# sunsensor.net
KiCad netlist of a schematic drawn in Altium Designer
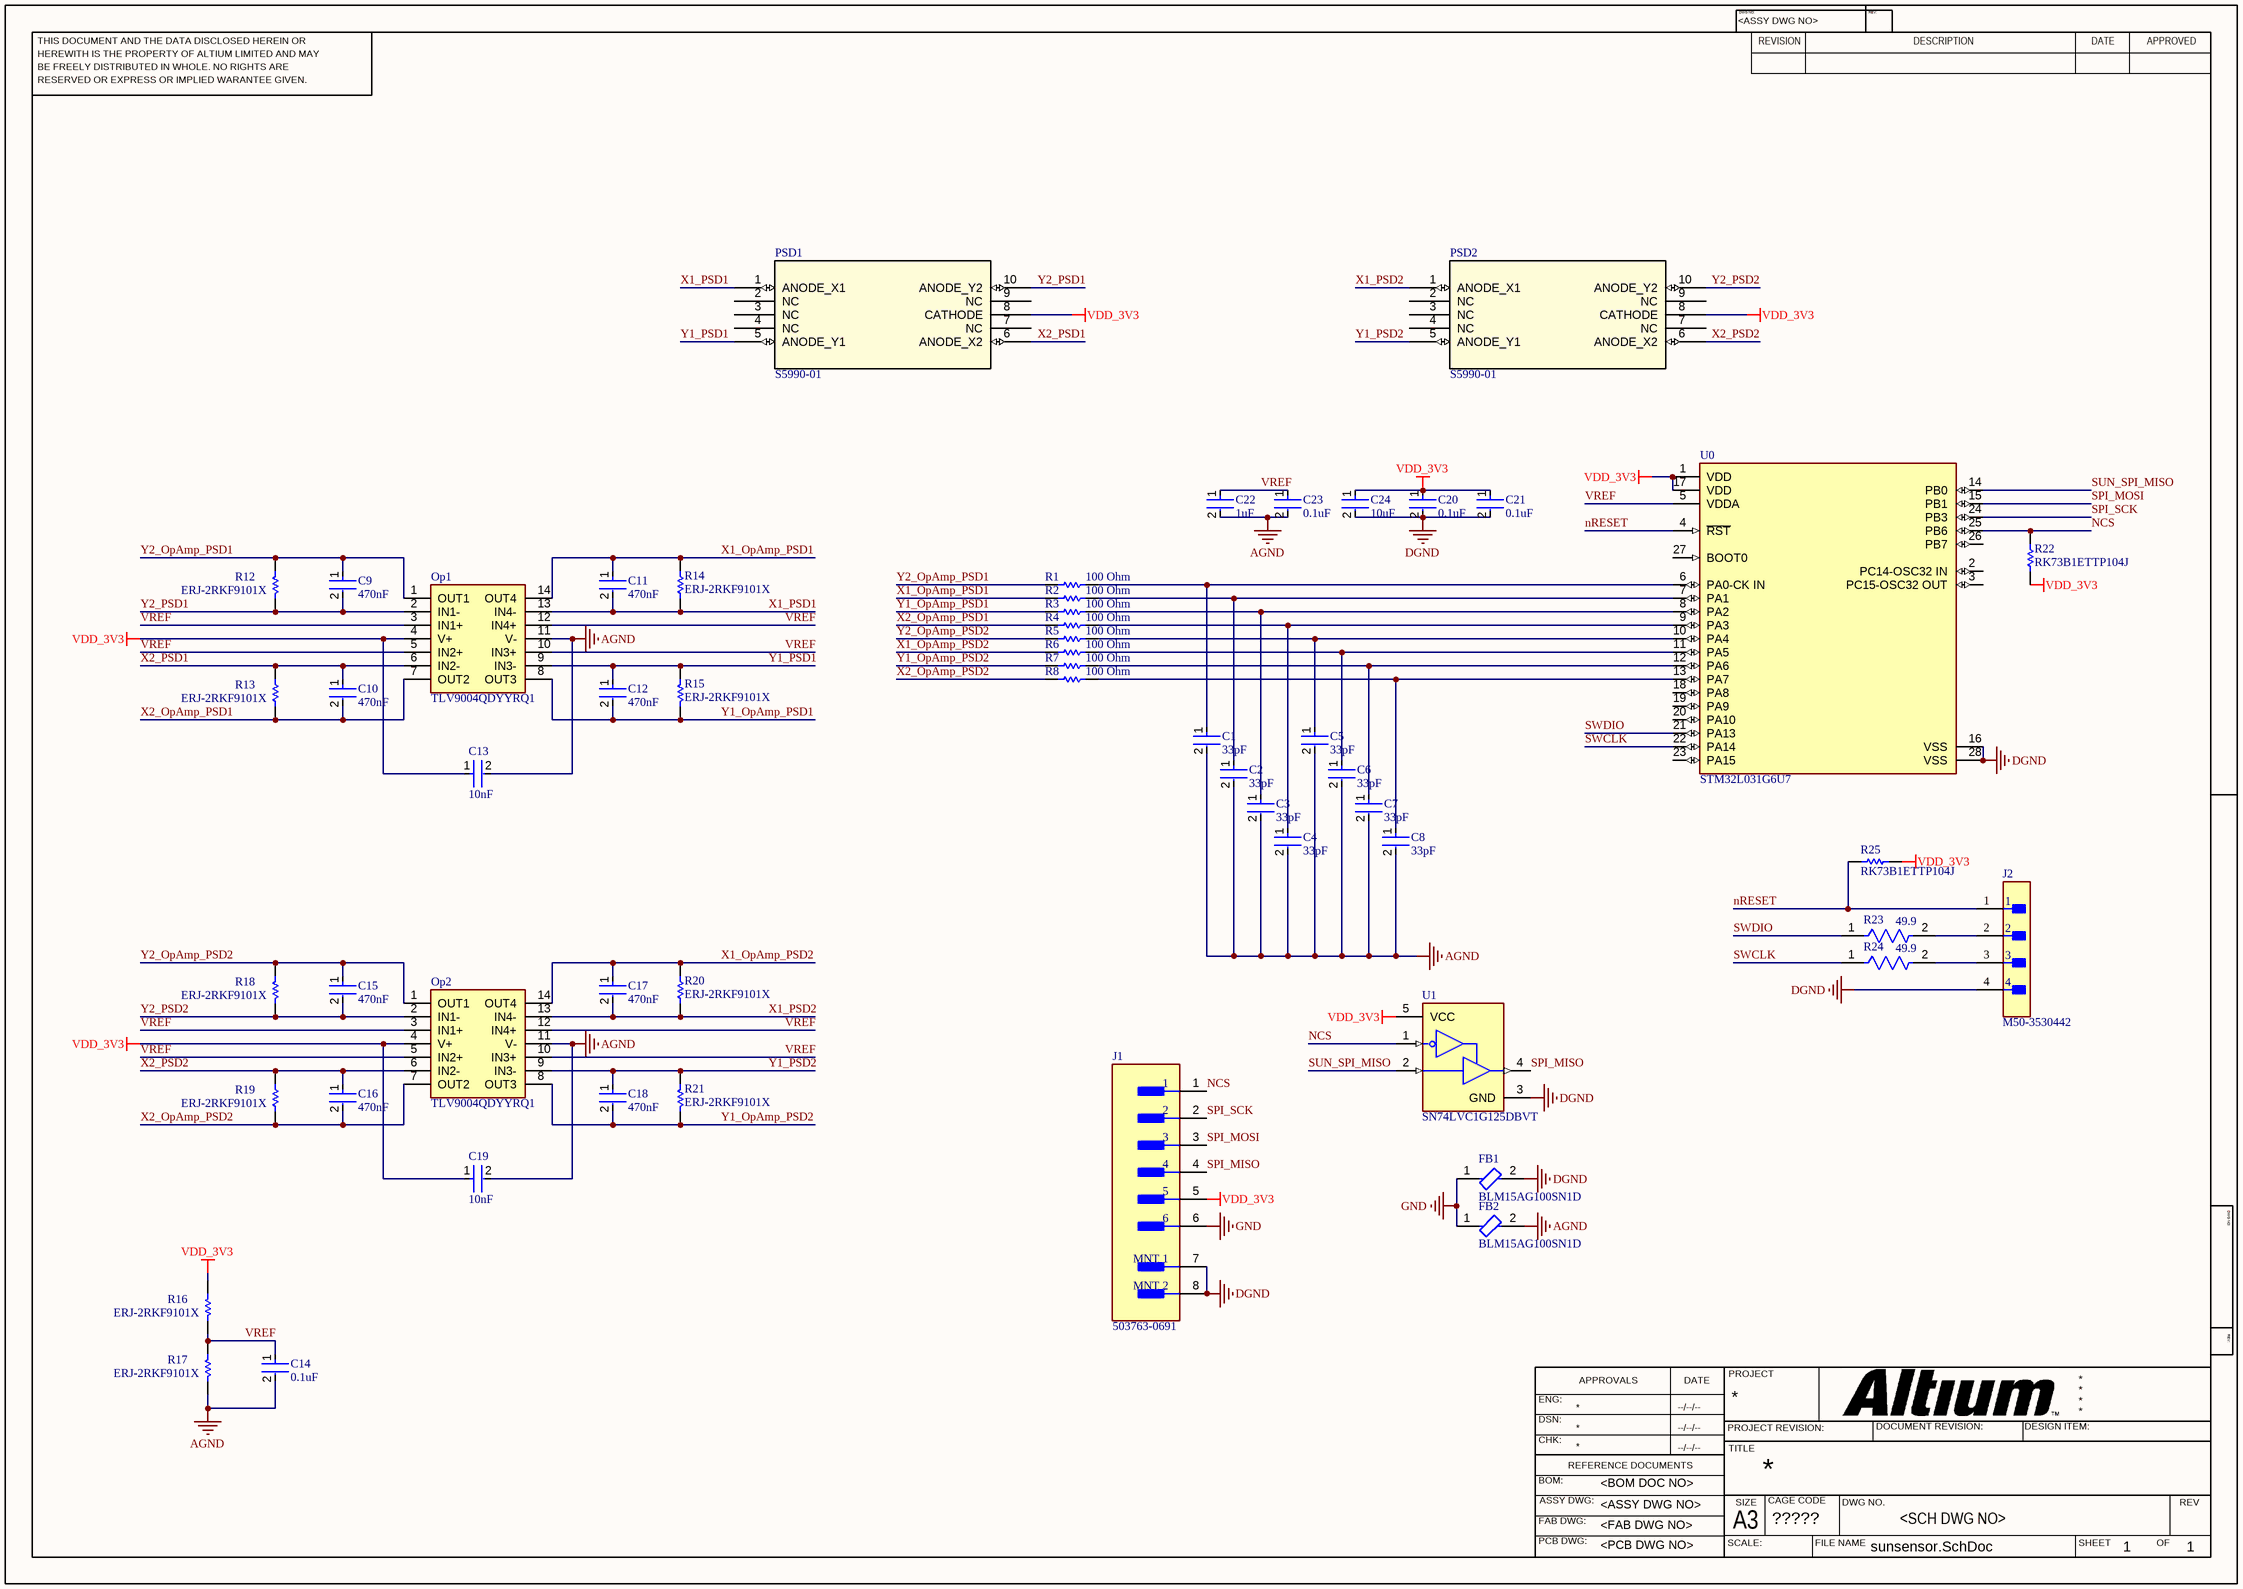
[diagram p0: sunsensor.SchDoc]

(export (version "E")
  (design (tool "Eeschema 10.0.6"))
  (components
    (comp (ref "C1")
      (value "33pF")
      (footprint "FP-C0402-BB-MFG")
      (description "CAP CER 33PF 50V C0G/NP0 0402")
      (fields (field (name "TOLERANCE") "0.01") (field (name "MANUFACTURER PART NUMBER") "C0402C330F5GACTU"))
      (libsource (lib "Altium Content Vault") (part "b4654b650e69147ec39a6b967a45e02"))
    )
    (comp (ref "C2")
      (value "33pF")
      (footprint "FP-C0402-BB-MFG")
      (description "CAP CER 33PF 50V C0G/NP0 0402")
      (fields (field (name "TOLERANCE") "0.01") (field (name "MANUFACTURER PART NUMBER") "C0402C330F5GACTU"))
      (libsource (lib "Altium Content Vault") (part "b4654b650e69147ec39a6b967a45e02"))
    )
    (comp (ref "C3")
      (value "33pF")
      (footprint "FP-C0402-BB-MFG")
      (description "CAP CER 33PF 50V C0G/NP0 0402")
      (fields (field (name "TOLERANCE") "0.01") (field (name "MANUFACTURER PART NUMBER") "C0402C330F5GACTU"))
      (libsource (lib "Altium Content Vault") (part "b4654b650e69147ec39a6b967a45e02"))
    )
    (comp (ref "C4")
      (value "33pF")
      (footprint "FP-C0402-BB-MFG")
      (description "CAP CER 33PF 50V C0G/NP0 0402")
      (fields (field (name "TOLERANCE") "0.01") (field (name "MANUFACTURER PART NUMBER") "C0402C330F5GACTU"))
      (libsource (lib "Altium Content Vault") (part "b4654b650e69147ec39a6b967a45e02"))
    )
    (comp (ref "C5")
      (value "33pF")
      (footprint "FP-C0402-BB-MFG")
      (description "CAP CER 33PF 50V C0G/NP0 0402")
      (fields (field (name "TOLERANCE") "0.01") (field (name "MANUFACTURER PART NUMBER") "C0402C330F5GACTU"))
      (libsource (lib "Altium Content Vault") (part "b4654b650e69147ec39a6b967a45e02"))
    )
    (comp (ref "C6")
      (value "33pF")
      (footprint "FP-C0402-BB-MFG")
      (description "CAP CER 33PF 50V C0G/NP0 0402")
      (fields (field (name "TOLERANCE") "0.01") (field (name "MANUFACTURER PART NUMBER") "C0402C330F5GACTU"))
      (libsource (lib "Altium Content Vault") (part "b4654b650e69147ec39a6b967a45e02"))
    )
    (comp (ref "C7")
      (value "33pF")
      (footprint "FP-C0402-BB-MFG")
      (description "CAP CER 33PF 50V C0G/NP0 0402")
      (fields (field (name "TOLERANCE") "0.01") (field (name "MANUFACTURER PART NUMBER") "C0402C330F5GACTU"))
      (libsource (lib "Altium Content Vault") (part "b4654b650e69147ec39a6b967a45e02"))
    )
    (comp (ref "C8")
      (value "33pF")
      (footprint "FP-C0402-BB-MFG")
      (description "CAP CER 33PF 50V C0G/NP0 0402")
      (fields (field (name "TOLERANCE") "0.01") (field (name "MANUFACTURER PART NUMBER") "C0402C330F5GACTU"))
      (libsource (lib "Altium Content Vault") (part "b4654b650e69147ec39a6b967a45e02"))
    )
    (comp (ref "C9")
      (value "470nF")
      (footprint "FP-GRM155-0_05-IPC_C")
      (description "Chip Multilayer Ceramic Capacitors for General Purpose, 0402, 0.47uF, X7R, 15%, 10%, 10V")
      (fields (field (name "TOLERANCE") "10%"))
      (libsource (lib "Altium Content Vault") (part "02cd4be3c70576c341d710602a673aa"))
    )
    (comp (ref "C10")
      (value "470nF")
      (footprint "FP-GRM155-0_05-IPC_C")
      (description "Chip Multilayer Ceramic Capacitors for General Purpose, 0402, 0.47uF, X7R, 15%, 10%, 10V")
      (fields (field (name "TOLERANCE") "10%"))
      (libsource (lib "Altium Content Vault") (part "02cd4be3c70576c341d710602a673aa"))
    )
    (comp (ref "C11")
      (value "470nF")
      (footprint "FP-GRM155-0_05-IPC_C")
      (description "Chip Multilayer Ceramic Capacitors for General Purpose, 0402, 0.47uF, X7R, 15%, 10%, 10V")
      (fields (field (name "TOLERANCE") "10%"))
      (libsource (lib "Altium Content Vault") (part "02cd4be3c70576c341d710602a673aa"))
    )
    (comp (ref "C12")
      (value "470nF")
      (footprint "FP-GRM155-0_05-IPC_C")
      (description "Chip Multilayer Ceramic Capacitors for General Purpose, 0402, 0.47uF, X7R, 15%, 10%, 10V")
      (fields (field (name "TOLERANCE") "10%"))
      (libsource (lib "Altium Content Vault") (part "02cd4be3c70576c341d710602a673aa"))
    )
    (comp (ref "C13")
      (value "10nF")
      (footprint "FP-C0402-BB-MFG")
      (description "CAP CER 10000PF 50V X7R 0402")
      (fields (field (name "TOLERANCE") "0.1") (field (name "MANUFACTURER") "Kemet"))
      (libsource (lib "Altium Content Vault") (part "b4654b650e69147ec39a6b967a45e02"))
    )
    (comp (ref "C14")
      (value "0.1uF")
      (footprint "FP-C0402-BB-MFG")
      (description "CAP CER 0.1UF 16V X7R 0402")
      (fields
        (field (name "TOLERANCE") "0.1")
        (field (name "OCTOPART") "https://octopart.com/c0402c104k4ractu-kemet-94158")
      )
      (libsource (lib "Altium Content Vault") (part "b4654b650e69147ec39a6b967a45e02"))
    )
    (comp (ref "C15")
      (value "470nF")
      (footprint "FP-GRM155-0_05-IPC_C")
      (description "Chip Multilayer Ceramic Capacitors for General Purpose, 0402, 0.47uF, X7R, 15%, 10%, 10V")
      (fields (field (name "TOLERANCE") "10%"))
      (libsource (lib "Altium Content Vault") (part "02cd4be3c70576c341d710602a673aa"))
    )
    (comp (ref "C16")
      (value "470nF")
      (footprint "FP-GRM155-0_05-IPC_C")
      (description "Chip Multilayer Ceramic Capacitors for General Purpose, 0402, 0.47uF, X7R, 15%, 10%, 10V")
      (fields (field (name "TOLERANCE") "10%"))
      (libsource (lib "Altium Content Vault") (part "02cd4be3c70576c341d710602a673aa"))
    )
    (comp (ref "C17")
      (value "470nF")
      (footprint "FP-GRM155-0_05-IPC_C")
      (description "Chip Multilayer Ceramic Capacitors for General Purpose, 0402, 0.47uF, X7R, 15%, 10%, 10V")
      (fields (field (name "TOLERANCE") "10%"))
      (libsource (lib "Altium Content Vault") (part "02cd4be3c70576c341d710602a673aa"))
    )
    (comp (ref "C18")
      (value "470nF")
      (footprint "FP-GRM155-0_05-IPC_C")
      (description "Chip Multilayer Ceramic Capacitors for General Purpose, 0402, 0.47uF, X7R, 15%, 10%, 10V")
      (fields (field (name "TOLERANCE") "10%"))
      (libsource (lib "Altium Content Vault") (part "02cd4be3c70576c341d710602a673aa"))
    )
    (comp (ref "C19")
      (value "10nF")
      (footprint "FP-C0402-BB-MFG")
      (description "CAP CER 10000PF 50V X7R 0402")
      (fields (field (name "TOLERANCE") "0.1") (field (name "MANUFACTURER") "Kemet"))
      (libsource (lib "Altium Content Vault") (part "b4654b650e69147ec39a6b967a45e02"))
    )
    (comp (ref "C20")
      (value "0.1uF")
      (footprint "FP-C0402-BB-MFG")
      (description "CAP CER 0.1UF 16V X7R 0402")
      (fields
        (field (name "TOLERANCE") "0.1")
        (field (name "OCTOPART") "https://octopart.com/c0402c104k4ractu-kemet-94158")
      )
      (libsource (lib "Altium Content Vault") (part "b4654b650e69147ec39a6b967a45e02"))
    )
    (comp (ref "C21")
      (value "0.1uF")
      (footprint "FP-C0402-BB-MFG")
      (description "CAP CER 0.1UF 16V X7R 0402")
      (fields
        (field (name "TOLERANCE") "0.1")
        (field (name "OCTOPART") "https://octopart.com/c0402c104k4ractu-kemet-94158")
      )
      (libsource (lib "Altium Content Vault") (part "b4654b650e69147ec39a6b967a45e02"))
    )
    (comp (ref "C22")
      (value "1uF")
      (footprint "FP-C0402C105K8PACTU-MFG")
      (description "CAP CER 1UF 10V X5R 0402")
      (fields (field (name "VOLTAGE") "10V") (field (name "TOLERANCE") "10%"))
      (libsource (lib "Altium Content Vault") (part "11868f565c42a9108669ba33697ecf6"))
    )
    (comp (ref "C23")
      (value "0.1uF")
      (footprint "FP-C0402-BB-MFG")
      (description "CAP CER 0.1UF 16V X7R 0402")
      (fields
        (field (name "TOLERANCE") "0.1")
        (field (name "OCTOPART") "https://octopart.com/c0402c104k4ractu-kemet-94158")
      )
      (libsource (lib "Altium Content Vault") (part "b4654b650e69147ec39a6b967a45e02"))
    )
    (comp (ref "C24")
      (value "10uF")
      (footprint "FP-C0402C106M9PACTU-MFG")
      (description "CAP CER 10UF 6.3V X5R 0402")
      (fields (field (name "TOLERANCE") "20%"))
      (libsource (lib "Altium Content Vault") (part "b4654b650e69147ec39a6b967a45e02"))
    )
    (comp (ref "FB1")
      (value "BLM15AG100SN1D")
      (footprint "FP-BLM15-0_05-IPC_A")
      (description "Chip Ferrite Bead, 0402, 10Ω @ 100MHz, 0.025Ω, 25%, 1A")
      (fields (field (name "TOLERANCE") "25%"))
      (libsource (lib "Altium Content Vault") (part "5f30dd21d616792df468990f7003faa"))
    )
    (comp (ref "FB2")
      (value "BLM15AG100SN1D")
      (footprint "FP-BLM15-0_05-IPC_A")
      (description "Chip Ferrite Bead, 0402, 10Ω @ 100MHz, 0.025Ω, 25%, 1A")
      (fields (field (name "TOLERANCE") "25%"))
      (libsource (lib "Altium Content Vault") (part "5f30dd21d616792df468990f7003faa"))
    )
    (comp (ref "J1")
      (value "503763-0691")
      (footprint "FP-503763-0691-MFG")
      (description "CONN HEADER SMD R/A 6POS 1MM")
      (libsource (lib "Altium Content Vault") (part "ed24c53d9ba001d1a2a686240a95171"))
    )
    (comp (ref "J2")
      (value "M50-3530442")
      (footprint "FP-M50-3530442-MFG")
      (description "CONN HEADER VERT 4POS 1.27MM")
      (libsource (lib "Altium Content Vault") (part "c01754ab0efc13afb7424b896f394ef"))
    )
    (comp (ref "Op1")
      (value "TLV9004QDYYRQ1")
      (footprint "SamacSys:SOP50P326X110-14N")
      (description "Integrated Circuit")
      (fields (field (name "MOUSER PART NUMBER") "595-TLV9004QDYYRQ1"))
      (libsource (lib "*") (part "TLV9004QDYYRQ1"))
    )
    (comp (ref "Op2")
      (value "TLV9004QDYYRQ1")
      (footprint "SamacSys:SOP50P326X110-14N")
      (description "Integrated Circuit")
      (fields (field (name "MOUSER PART NUMBER") "595-TLV9004QDYYRQ1"))
      (libsource (lib "*") (part "TLV9004QDYYRQ1"))
    )
    (comp (ref "PSD1")
      (value "S5990-01")
      (footprint "S5990_HAM")
      (description "No Description Available")
      (libsource (lib "Hitesh Bhoyar") (part "S5990-01"))
    )
    (comp (ref "PSD2")
      (value "S5990-01")
      (footprint "S5990_HAM")
      (description "No Description Available")
      (libsource (lib "Hitesh Bhoyar") (part "S5990-01"))
    )
    (comp (ref "R1")
      (value "100 Ohm")
      (footprint "RESC1005X40X25ML05T10")
      (fields (field (name "PART NUMBER") "ERJ-U02F1000X") (field (name "MANUFACTURER") "Panasonic"))
      (libsource (lib "Altium Content Vault") (part "RES"))
    )
    (comp (ref "R2")
      (value "100 Ohm")
      (footprint "RESC1005X40X25ML05T10")
      (fields (field (name "PART NUMBER") "ERJ-U02F1000X") (field (name "MANUFACTURER") "Panasonic"))
      (libsource (lib "Altium Content Vault") (part "RES"))
    )
    (comp (ref "R3")
      (value "100 Ohm")
      (footprint "RESC1005X40X25ML05T10")
      (fields (field (name "PART NUMBER") "ERJ-U02F1000X") (field (name "MANUFACTURER") "Panasonic"))
      (libsource (lib "Altium Content Vault") (part "RES"))
    )
    (comp (ref "R4")
      (value "100 Ohm")
      (footprint "RESC1005X40X25ML05T10")
      (fields (field (name "PART NUMBER") "ERJ-U02F1000X") (field (name "MANUFACTURER") "Panasonic"))
      (libsource (lib "Altium Content Vault") (part "RES"))
    )
    (comp (ref "R5")
      (value "100 Ohm")
      (footprint "RESC1005X40X25ML05T10")
      (fields (field (name "PART NUMBER") "ERJ-U02F1000X") (field (name "MANUFACTURER") "Panasonic"))
      (libsource (lib "Altium Content Vault") (part "RES"))
    )
    (comp (ref "R6")
      (value "100 Ohm")
      (footprint "RESC1005X40X25ML05T10")
      (fields (field (name "PART NUMBER") "ERJ-U02F1000X") (field (name "MANUFACTURER") "Panasonic"))
      (libsource (lib "Altium Content Vault") (part "RES"))
    )
    (comp (ref "R7")
      (value "100 Ohm")
      (footprint "RESC1005X40X25ML05T10")
      (fields (field (name "PART NUMBER") "ERJ-U02F1000X") (field (name "MANUFACTURER") "Panasonic"))
      (libsource (lib "Altium Content Vault") (part "RES"))
    )
    (comp (ref "R8")
      (value "100 Ohm")
      (footprint "RESC1005X40X25ML05T10")
      (fields (field (name "PART NUMBER") "ERJ-U02F1000X") (field (name "MANUFACTURER") "Panasonic"))
      (libsource (lib "Altium Content Vault") (part "RES"))
    )
    (comp (ref "R12")
      (value "ERJ-2RKF9101X")
      (footprint "RESC1005X40X25LL05T05")
      (fields (field (name "MANUFACTURER") "Panasonic"))
      (libsource (lib "Altium Content Vault") (part "RES"))
    )
    (comp (ref "R13")
      (value "ERJ-2RKF9101X")
      (footprint "RESC1005X40X25LL05T05")
      (fields (field (name "MANUFACTURER") "Panasonic"))
      (libsource (lib "Altium Content Vault") (part "RES"))
    )
    (comp (ref "R14")
      (value "ERJ-2RKF9101X")
      (footprint "RESC1005X40X25LL05T05")
      (fields (field (name "MANUFACTURER") "Panasonic"))
      (libsource (lib "Altium Content Vault") (part "RES"))
    )
    (comp (ref "R15")
      (value "ERJ-2RKF9101X")
      (footprint "RESC1005X40X25LL05T05")
      (fields (field (name "MANUFACTURER") "Panasonic"))
      (libsource (lib "Altium Content Vault") (part "RES"))
    )
    (comp (ref "R16")
      (value "ERJ-2RKF9101X")
      (footprint "RESC1005X40X25LL05T05")
      (fields (field (name "MANUFACTURER") "Panasonic"))
      (libsource (lib "Altium Content Vault") (part "RES"))
    )
    (comp (ref "R17")
      (value "ERJ-2RKF9101X")
      (footprint "RESC1005X40X25LL05T05")
      (fields (field (name "MANUFACTURER") "Panasonic"))
      (libsource (lib "Altium Content Vault") (part "RES"))
    )
    (comp (ref "R18")
      (value "ERJ-2RKF9101X")
      (footprint "RESC1005X40X25LL05T05")
      (fields (field (name "MANUFACTURER") "Panasonic"))
      (libsource (lib "Altium Content Vault") (part "RES"))
    )
    (comp (ref "R19")
      (value "ERJ-2RKF9101X")
      (footprint "RESC1005X40X25LL05T05")
      (fields (field (name "MANUFACTURER") "Panasonic"))
      (libsource (lib "Altium Content Vault") (part "RES"))
    )
    (comp (ref "R20")
      (value "ERJ-2RKF9101X")
      (footprint "RESC1005X40X25LL05T05")
      (fields (field (name "MANUFACTURER") "Panasonic"))
      (libsource (lib "Altium Content Vault") (part "RES"))
    )
    (comp (ref "R21")
      (value "ERJ-2RKF9101X")
      (footprint "RESC1005X40X25LL05T05")
      (fields (field (name "MANUFACTURER") "Panasonic"))
      (libsource (lib "Altium Content Vault") (part "RES"))
    )
    (comp (ref "R22")
      (value "RK73B1ETTP104J")
      (footprint "RESC1005X40X25ML10T10")
      (fields (field (name "MANUFACTURER") "KOA Speer"))
      (libsource (lib "Altium Content Vault") (part "RES"))
    )
    (comp (ref "R23")
      (value "49.9")
      (footprint "FP-ERJ2RK-MFG")
      (description "RES SMD 49.9 OHM 1% 1/10W 0402")
      (fields (field (name "TOLERANCE") "1%"))
      (libsource (lib "Altium Content Vault") (part "8db39607336c341a927600551d01821"))
    )
    (comp (ref "R24")
      (value "49.9")
      (footprint "FP-ERJ2RK-MFG")
      (description "RES SMD 49.9 OHM 1% 1/10W 0402")
      (fields (field (name "TOLERANCE") "1%"))
      (libsource (lib "Altium Content Vault") (part "8db39607336c341a927600551d01821"))
    )
    (comp (ref "R25")
      (value "RK73B1ETTP104J")
      (footprint "RESC1005X40X25ML10T10")
      (fields (field (name "MANUFACTURER") "KOA Speer"))
      (libsource (lib "Altium Content Vault") (part "RES"))
    )
    (comp (ref "U0")
      (value "STM32L031G6U7")
      (footprint "FP-UFQFPN28-A0B0-MFG")
      (description "IC MCU 32BIT 32KB FLASH 28UFQFPN")
      (libsource (lib "Altium Content Vault") (part "cf8d419c7f1ef5ba6492875b64af71c"))
    )
    (comp (ref "U1")
      (value "SN74LVC1G125DBVT")
      (footprint "FP-DBV0005A-MFG")
      (description "IC BUF NON-INVERT 5.5V SOT23-5")
      (fields
        (field (name "OCTOPART") "https://octopart.com/sn74lvc1g125dbvt-texas+instruments-1006799")
        (field (name "MANUFACTURER") "Texas Instruments")
      )
      (libsource (lib "Altium Content Vault") (part "58769f6d8490b1ac5b52b989db43374"))
    )
  )
  (nets
    (net (code "1") (name "/NCS") (class "Default")
      (node (ref "J1") (pin "1") (pinfunction "1_1") (pintype "passive"))
      (node (ref "R22") (pin "2") (pinfunction "2_2") (pintype "passive"))
      (node (ref "U0") (pin "25") (pinfunction "PB6_25") (pintype "bidirectional"))
      (node (ref "U1") (pin "1") (pinfunction "~{OE}_1") (pintype "input"))
    )
    (net (code "2") (name "/SPI_MISO") (class "Default")
      (node (ref "J1") (pin "4") (pinfunction "4_4") (pintype "passive"))
      (node (ref "U1") (pin "4") (pinfunction "Y_4") (pintype "output"))
    )
    (net (code "3") (name "/SPI_MOSI") (class "Default")
      (node (ref "J1") (pin "3") (pinfunction "3_3") (pintype "passive"))
      (node (ref "U0") (pin "15") (pinfunction "PB1_15") (pintype "bidirectional"))
    )
    (net (code "4") (name "/SPI_SCK") (class "Default")
      (node (ref "J1") (pin "2") (pinfunction "2_2") (pintype "passive"))
      (node (ref "U0") (pin "24") (pinfunction "PB3_24") (pintype "bidirectional"))
    )
    (net (code "5") (name "/SUN_SPI_MISO") (class "Default")
      (node (ref "U0") (pin "14") (pinfunction "PB0_14") (pintype "bidirectional"))
      (node (ref "U1") (pin "2") (pinfunction "A_2") (pintype "input"))
    )
    (net (code "6") (name "/SWCLK") (class "Default")
      (node (ref "R24") (pin "1") (pinfunction "1_1") (pintype "passive"))
      (node (ref "U0") (pin "22") (pinfunction "PA14_22") (pintype "bidirectional"))
    )
    (net (code "7") (name "/SWDIO") (class "Default")
      (node (ref "R23") (pin "1") (pinfunction "1_1") (pintype "passive"))
      (node (ref "U0") (pin "21") (pinfunction "PA13_21") (pintype "bidirectional"))
    )
    (net (code "8") (name "/VREF") (class "Default")
      (node (ref "C14") (pin "1") (pinfunction "1_1") (pintype "passive"))
      (node (ref "C22") (pin "1") (pinfunction "1_1") (pintype "passive"))
      (node (ref "C23") (pin "1") (pinfunction "1_1") (pintype "passive"))
      (node (ref "Op1") (pin "10") (pinfunction "IN3+_10") (pintype "passive"))
      (node (ref "Op1") (pin "12") (pinfunction "IN4+_12") (pintype "passive"))
      (node (ref "Op1") (pin "3") (pinfunction "IN1+_3") (pintype "passive"))
      (node (ref "Op1") (pin "5") (pinfunction "IN2+_5") (pintype "passive"))
      (node (ref "Op2") (pin "10") (pinfunction "IN3+_10") (pintype "passive"))
      (node (ref "Op2") (pin "12") (pinfunction "IN4+_12") (pintype "passive"))
      (node (ref "Op2") (pin "3") (pinfunction "IN1+_3") (pintype "passive"))
      (node (ref "Op2") (pin "5") (pinfunction "IN2+_5") (pintype "passive"))
      (node (ref "R16") (pin "1") (pinfunction "1_1") (pintype "passive"))
      (node (ref "R17") (pin "2") (pinfunction "2_2") (pintype "passive"))
      (node (ref "U0") (pin "5") (pinfunction "VDDA_5") (pintype "power_in"))
    )
    (net (code "9") (name "/X1_OpAmp_PSD1") (class "Default")
      (node (ref "C11") (pin "1") (pinfunction "1_1") (pintype "passive"))
      (node (ref "Op1") (pin "14") (pinfunction "OUT4_14") (pintype "passive"))
      (node (ref "R14") (pin "2") (pinfunction "2_2") (pintype "passive"))
      (node (ref "R2") (pin "1") (pinfunction "1_1") (pintype "passive"))
    )
    (net (code "10") (name "/X1_OpAmp_PSD2") (class "Default")
      (node (ref "C17") (pin "1") (pinfunction "1_1") (pintype "passive"))
      (node (ref "Op2") (pin "14") (pinfunction "OUT4_14") (pintype "passive"))
      (node (ref "R20") (pin "2") (pinfunction "2_2") (pintype "passive"))
      (node (ref "R6") (pin "1") (pinfunction "1_1") (pintype "passive"))
    )
    (net (code "11") (name "/X1_PSD1") (class "Default")
      (node (ref "C11") (pin "2") (pinfunction "2_2") (pintype "passive"))
      (node (ref "Op1") (pin "13") (pinfunction "IN4-_13") (pintype "passive"))
      (node (ref "PSD1") (pin "1") (pinfunction "ANODE_X1_1") (pintype "bidirectional"))
      (node (ref "R14") (pin "1") (pinfunction "1_1") (pintype "passive"))
    )
    (net (code "12") (name "/X1_PSD2") (class "Default")
      (node (ref "C17") (pin "2") (pinfunction "2_2") (pintype "passive"))
      (node (ref "Op2") (pin "13") (pinfunction "IN4-_13") (pintype "passive"))
      (node (ref "PSD2") (pin "1") (pinfunction "ANODE_X1_1") (pintype "bidirectional"))
      (node (ref "R20") (pin "1") (pinfunction "1_1") (pintype "passive"))
    )
    (net (code "13") (name "/X2_OpAmp_PSD1") (class "Default")
      (node (ref "C10") (pin "2") (pinfunction "2_2") (pintype "passive"))
      (node (ref "Op1") (pin "7") (pinfunction "OUT2_7") (pintype "passive"))
      (node (ref "R13") (pin "2") (pinfunction "2_2") (pintype "passive"))
      (node (ref "R4") (pin "1") (pinfunction "1_1") (pintype "passive"))
    )
    (net (code "14") (name "/X2_OpAmp_PSD2") (class "Default")
      (node (ref "C16") (pin "2") (pinfunction "2_2") (pintype "passive"))
      (node (ref "Op2") (pin "7") (pinfunction "OUT2_7") (pintype "passive"))
      (node (ref "R19") (pin "2") (pinfunction "2_2") (pintype "passive"))
      (node (ref "R8") (pin "1") (pinfunction "1_1") (pintype "passive"))
    )
    (net (code "15") (name "/X2_PSD1") (class "Default")
      (node (ref "C10") (pin "1") (pinfunction "1_1") (pintype "passive"))
      (node (ref "Op1") (pin "6") (pinfunction "IN2-_6") (pintype "passive"))
      (node (ref "PSD1") (pin "6") (pinfunction "ANODE_X2_6") (pintype "bidirectional"))
      (node (ref "R13") (pin "1") (pinfunction "1_1") (pintype "passive"))
    )
    (net (code "16") (name "/X2_PSD2") (class "Default")
      (node (ref "C16") (pin "1") (pinfunction "1_1") (pintype "passive"))
      (node (ref "Op2") (pin "6") (pinfunction "IN2-_6") (pintype "passive"))
      (node (ref "PSD2") (pin "6") (pinfunction "ANODE_X2_6") (pintype "bidirectional"))
      (node (ref "R19") (pin "1") (pinfunction "1_1") (pintype "passive"))
    )
    (net (code "17") (name "/Y1_OpAmp_PSD1") (class "Default")
      (node (ref "C12") (pin "2") (pinfunction "2_2") (pintype "passive"))
      (node (ref "Op1") (pin "8") (pinfunction "OUT3_8") (pintype "passive"))
      (node (ref "R15") (pin "2") (pinfunction "2_2") (pintype "passive"))
      (node (ref "R3") (pin "1") (pinfunction "1_1") (pintype "passive"))
    )
    (net (code "18") (name "/Y1_OpAmp_PSD2") (class "Default")
      (node (ref "C18") (pin "2") (pinfunction "2_2") (pintype "passive"))
      (node (ref "Op2") (pin "8") (pinfunction "OUT3_8") (pintype "passive"))
      (node (ref "R21") (pin "2") (pinfunction "2_2") (pintype "passive"))
      (node (ref "R7") (pin "1") (pinfunction "1_1") (pintype "passive"))
    )
    (net (code "19") (name "/Y1_PSD1") (class "Default")
      (node (ref "C12") (pin "1") (pinfunction "1_1") (pintype "passive"))
      (node (ref "Op1") (pin "9") (pinfunction "IN3-_9") (pintype "passive"))
      (node (ref "PSD1") (pin "5") (pinfunction "ANODE_Y1_5") (pintype "bidirectional"))
      (node (ref "R15") (pin "1") (pinfunction "1_1") (pintype "passive"))
    )
    (net (code "20") (name "/Y1_PSD2") (class "Default")
      (node (ref "C18") (pin "1") (pinfunction "1_1") (pintype "passive"))
      (node (ref "Op2") (pin "9") (pinfunction "IN3-_9") (pintype "passive"))
      (node (ref "PSD2") (pin "5") (pinfunction "ANODE_Y1_5") (pintype "bidirectional"))
      (node (ref "R21") (pin "1") (pinfunction "1_1") (pintype "passive"))
    )
    (net (code "21") (name "/Y2_OpAmp_PSD1") (class "Default")
      (node (ref "C9") (pin "1") (pinfunction "1_1") (pintype "passive"))
      (node (ref "Op1") (pin "1") (pinfunction "OUT1_1") (pintype "passive"))
      (node (ref "R1") (pin "1") (pinfunction "1_1") (pintype "passive"))
      (node (ref "R12") (pin "2") (pinfunction "2_2") (pintype "passive"))
    )
    (net (code "22") (name "/Y2_OpAmp_PSD2") (class "Default")
      (node (ref "C15") (pin "1") (pinfunction "1_1") (pintype "passive"))
      (node (ref "Op2") (pin "1") (pinfunction "OUT1_1") (pintype "passive"))
      (node (ref "R18") (pin "2") (pinfunction "2_2") (pintype "passive"))
      (node (ref "R5") (pin "1") (pinfunction "1_1") (pintype "passive"))
    )
    (net (code "23") (name "/Y2_PSD1") (class "Default")
      (node (ref "C9") (pin "2") (pinfunction "2_2") (pintype "passive"))
      (node (ref "Op1") (pin "2") (pinfunction "IN1-_2") (pintype "passive"))
      (node (ref "PSD1") (pin "10") (pinfunction "ANODE_Y2_10") (pintype "bidirectional"))
      (node (ref "R12") (pin "1") (pinfunction "1_1") (pintype "passive"))
    )
    (net (code "24") (name "/Y2_PSD2") (class "Default")
      (node (ref "C15") (pin "2") (pinfunction "2_2") (pintype "passive"))
      (node (ref "Op2") (pin "2") (pinfunction "IN1-_2") (pintype "passive"))
      (node (ref "PSD2") (pin "10") (pinfunction "ANODE_Y2_10") (pintype "bidirectional"))
      (node (ref "R18") (pin "1") (pinfunction "1_1") (pintype "passive"))
    )
    (net (code "25") (name "/nRESET") (class "Default")
      (node (ref "J2") (pin "1") (pinfunction "1_1") (pintype "passive"))
      (node (ref "R25") (pin "2") (pinfunction "2_2") (pintype "passive"))
      (node (ref "U0") (pin "4") (pinfunction "~{RST}_4") (pintype "input"))
    )
    (net (code "26") (name "AGND") (class "Default")
      (node (ref "C1") (pin "2") (pinfunction "2_2") (pintype "passive"))
      (node (ref "C13") (pin "2") (pinfunction "2_2") (pintype "passive"))
      (node (ref "C14") (pin "2") (pinfunction "2_2") (pintype "passive"))
      (node (ref "C19") (pin "2") (pinfunction "2_2") (pintype "passive"))
      (node (ref "C2") (pin "2") (pinfunction "2_2") (pintype "passive"))
      (node (ref "C22") (pin "2") (pinfunction "2_2") (pintype "passive"))
      (node (ref "C23") (pin "2") (pinfunction "2_2") (pintype "passive"))
      (node (ref "C3") (pin "2") (pinfunction "2_2") (pintype "passive"))
      (node (ref "C4") (pin "2") (pinfunction "2_2") (pintype "passive"))
      (node (ref "C5") (pin "2") (pinfunction "2_2") (pintype "passive"))
      (node (ref "C6") (pin "2") (pinfunction "2_2") (pintype "passive"))
      (node (ref "C7") (pin "2") (pinfunction "2_2") (pintype "passive"))
      (node (ref "C8") (pin "2") (pinfunction "2_2") (pintype "passive"))
      (node (ref "FB2") (pin "2") (pinfunction "2_2") (pintype "passive"))
      (node (ref "Op1") (pin "11") (pinfunction "V-_11") (pintype "passive"))
      (node (ref "Op2") (pin "11") (pinfunction "V-_11") (pintype "passive"))
      (node (ref "R17") (pin "1") (pinfunction "1_1") (pintype "passive"))
    )
    (net (code "27") (name "DGND") (class "Default")
      (node (ref "C20") (pin "2") (pinfunction "2_2") (pintype "passive"))
      (node (ref "C21") (pin "2") (pinfunction "2_2") (pintype "passive"))
      (node (ref "C24") (pin "2") (pinfunction "2_2") (pintype "passive"))
      (node (ref "FB1") (pin "2") (pinfunction "2_2") (pintype "passive"))
      (node (ref "J1") (pin "7") (pinfunction "MNT_1_7") (pintype "passive"))
      (node (ref "J1") (pin "8") (pinfunction "MNT_2_8") (pintype "passive"))
      (node (ref "J2") (pin "4") (pinfunction "4_4") (pintype "passive"))
      (node (ref "U0") (pin "16") (pinfunction "VSS_16") (pintype "power_in"))
      (node (ref "U0") (pin "28") (pinfunction "VSS_28") (pintype "power_in"))
      (node (ref "U1") (pin "3") (pinfunction "GND_3") (pintype "power_in"))
    )
    (net (code "28") (name "GND") (class "Default")
      (node (ref "FB1") (pin "1") (pinfunction "1_1") (pintype "passive"))
      (node (ref "FB2") (pin "1") (pinfunction "1_1") (pintype "passive"))
      (node (ref "J1") (pin "6") (pinfunction "6_6") (pintype "passive"))
    )
    (net (code "29") (name "Net-(J2-Pad2)") (class "Default")
      (node (ref "J2") (pin "2") (pinfunction "2_2") (pintype "passive"))
      (node (ref "R23") (pin "2") (pinfunction "2_2") (pintype "passive"))
    )
    (net (code "30") (name "Net-(J2-Pad3)") (class "Default")
      (node (ref "J2") (pin "3") (pinfunction "3_3") (pintype "passive"))
      (node (ref "R24") (pin "2") (pinfunction "2_2") (pintype "passive"))
    )
    (net (code "31") (name "Net-(U0-PA0-CK_IN)") (class "Default")
      (node (ref "C1") (pin "1") (pinfunction "1_1") (pintype "passive"))
      (node (ref "R1") (pin "2") (pinfunction "2_2") (pintype "passive"))
      (node (ref "U0") (pin "6") (pinfunction "PA0-CK_IN_6") (pintype "bidirectional"))
    )
    (net (code "32") (name "Net-(U0-PA1)") (class "Default")
      (node (ref "C2") (pin "1") (pinfunction "1_1") (pintype "passive"))
      (node (ref "R2") (pin "2") (pinfunction "2_2") (pintype "passive"))
      (node (ref "U0") (pin "7") (pinfunction "PA1_7") (pintype "bidirectional"))
    )
    (net (code "33") (name "Net-(U0-PA2)") (class "Default")
      (node (ref "C3") (pin "1") (pinfunction "1_1") (pintype "passive"))
      (node (ref "R3") (pin "2") (pinfunction "2_2") (pintype "passive"))
      (node (ref "U0") (pin "8") (pinfunction "PA2_8") (pintype "bidirectional"))
    )
    (net (code "34") (name "Net-(U0-PA3)") (class "Default")
      (node (ref "C4") (pin "1") (pinfunction "1_1") (pintype "passive"))
      (node (ref "R4") (pin "2") (pinfunction "2_2") (pintype "passive"))
      (node (ref "U0") (pin "9") (pinfunction "PA3_9") (pintype "bidirectional"))
    )
    (net (code "35") (name "Net-(U0-PA4)") (class "Default")
      (node (ref "C5") (pin "1") (pinfunction "1_1") (pintype "passive"))
      (node (ref "R5") (pin "2") (pinfunction "2_2") (pintype "passive"))
      (node (ref "U0") (pin "10") (pinfunction "PA4_10") (pintype "bidirectional"))
    )
    (net (code "36") (name "Net-(U0-PA5)") (class "Default")
      (node (ref "C6") (pin "1") (pinfunction "1_1") (pintype "passive"))
      (node (ref "R6") (pin "2") (pinfunction "2_2") (pintype "passive"))
      (node (ref "U0") (pin "11") (pinfunction "PA5_11") (pintype "bidirectional"))
    )
    (net (code "37") (name "Net-(U0-PA6)") (class "Default")
      (node (ref "C7") (pin "1") (pinfunction "1_1") (pintype "passive"))
      (node (ref "R7") (pin "2") (pinfunction "2_2") (pintype "passive"))
      (node (ref "U0") (pin "12") (pinfunction "PA6_12") (pintype "bidirectional"))
    )
    (net (code "38") (name "Net-(U0-PA7)") (class "Default")
      (node (ref "C8") (pin "1") (pinfunction "1_1") (pintype "passive"))
      (node (ref "R8") (pin "2") (pinfunction "2_2") (pintype "passive"))
      (node (ref "U0") (pin "13") (pinfunction "PA7_13") (pintype "bidirectional"))
    )
    (net (code "39") (name "VDD_3V3") (class "Default")
      (node (ref "C13") (pin "1") (pinfunction "1_1") (pintype "passive"))
      (node (ref "C19") (pin "1") (pinfunction "1_1") (pintype "passive"))
      (node (ref "C20") (pin "1") (pinfunction "1_1") (pintype "passive"))
      (node (ref "C21") (pin "1") (pinfunction "1_1") (pintype "passive"))
      (node (ref "C24") (pin "1") (pinfunction "1_1") (pintype "passive"))
      (node (ref "J1") (pin "5") (pinfunction "5_5") (pintype "passive"))
      (node (ref "Op1") (pin "4") (pinfunction "V+_4") (pintype "passive"))
      (node (ref "Op2") (pin "4") (pinfunction "V+_4") (pintype "passive"))
      (node (ref "PSD1") (pin "8") (pinfunction "CATHODE_8") (pintype "passive"))
      (node (ref "PSD2") (pin "8") (pinfunction "CATHODE_8") (pintype "passive"))
      (node (ref "R16") (pin "2") (pinfunction "2_2") (pintype "passive"))
      (node (ref "R22") (pin "1") (pinfunction "1_1") (pintype "passive"))
      (node (ref "R25") (pin "1") (pinfunction "1_1") (pintype "passive"))
      (node (ref "U0") (pin "1") (pinfunction "VDD_1") (pintype "power_in"))
      (node (ref "U0") (pin "17") (pinfunction "VDD_17") (pintype "power_in"))
      (node (ref "U1") (pin "5") (pinfunction "VCC_5") (pintype "power_in"))
    )
    (net (code "40") (name "unconnected-(PSD1-NC-Pad2)") (class "Default")
      (node (ref "PSD1") (pin "2") (pinfunction "NC_2") (pintype "passive"))
    )
    (net (code "41") (name "unconnected-(PSD1-NC-Pad3)") (class "Default")
      (node (ref "PSD1") (pin "3") (pinfunction "NC_3") (pintype "passive"))
    )
    (net (code "42") (name "unconnected-(PSD1-NC-Pad4)") (class "Default")
      (node (ref "PSD1") (pin "4") (pinfunction "NC_4") (pintype "passive"))
    )
    (net (code "43") (name "unconnected-(PSD1-NC-Pad7)") (class "Default")
      (node (ref "PSD1") (pin "7") (pinfunction "NC_7") (pintype "passive"))
    )
    (net (code "44") (name "unconnected-(PSD1-NC-Pad9)") (class "Default")
      (node (ref "PSD1") (pin "9") (pinfunction "NC_9") (pintype "passive"))
    )
    (net (code "45") (name "unconnected-(PSD2-NC-Pad2)") (class "Default")
      (node (ref "PSD2") (pin "2") (pinfunction "NC_2") (pintype "passive"))
    )
    (net (code "46") (name "unconnected-(PSD2-NC-Pad3)") (class "Default")
      (node (ref "PSD2") (pin "3") (pinfunction "NC_3") (pintype "passive"))
    )
    (net (code "47") (name "unconnected-(PSD2-NC-Pad4)") (class "Default")
      (node (ref "PSD2") (pin "4") (pinfunction "NC_4") (pintype "passive"))
    )
    (net (code "48") (name "unconnected-(PSD2-NC-Pad7)") (class "Default")
      (node (ref "PSD2") (pin "7") (pinfunction "NC_7") (pintype "passive"))
    )
    (net (code "49") (name "unconnected-(PSD2-NC-Pad9)") (class "Default")
      (node (ref "PSD2") (pin "9") (pinfunction "NC_9") (pintype "passive"))
    )
    (net (code "50") (name "unconnected-(U0-BOOT0-Pad27)") (class "Default")
      (node (ref "U0") (pin "27") (pinfunction "BOOT0_27") (pintype "input"))
    )
    (net (code "51") (name "unconnected-(U0-PA8-Pad18)") (class "Default")
      (node (ref "U0") (pin "18") (pinfunction "PA8_18") (pintype "bidirectional"))
    )
    (net (code "52") (name "unconnected-(U0-PA9-Pad19)") (class "Default")
      (node (ref "U0") (pin "19") (pinfunction "PA9_19") (pintype "bidirectional"))
    )
    (net (code "53") (name "unconnected-(U0-PA10-Pad20)") (class "Default")
      (node (ref "U0") (pin "20") (pinfunction "PA10_20") (pintype "bidirectional"))
    )
    (net (code "54") (name "unconnected-(U0-PA15-Pad23)") (class "Default")
      (node (ref "U0") (pin "23") (pinfunction "PA15_23") (pintype "bidirectional"))
    )
    (net (code "55") (name "unconnected-(U0-PB7-Pad26)") (class "Default")
      (node (ref "U0") (pin "26") (pinfunction "PB7_26") (pintype "bidirectional"))
    )
    (net (code "56") (name "unconnected-(U0-PC14-OSC32_IN-Pad2)") (class "Default")
      (node (ref "U0") (pin "2") (pinfunction "PC14-OSC32_IN_2") (pintype "bidirectional"))
    )
    (net (code "57") (name "unconnected-(U0-PC15-OSC32_OUT-Pad3)") (class "Default")
      (node (ref "U0") (pin "3") (pinfunction "PC15-OSC32_OUT_3") (pintype "bidirectional"))
    )
  )
)
